# hvSdbSchematic.net
KiCad netlist of a schematic drawn in Altium Designer
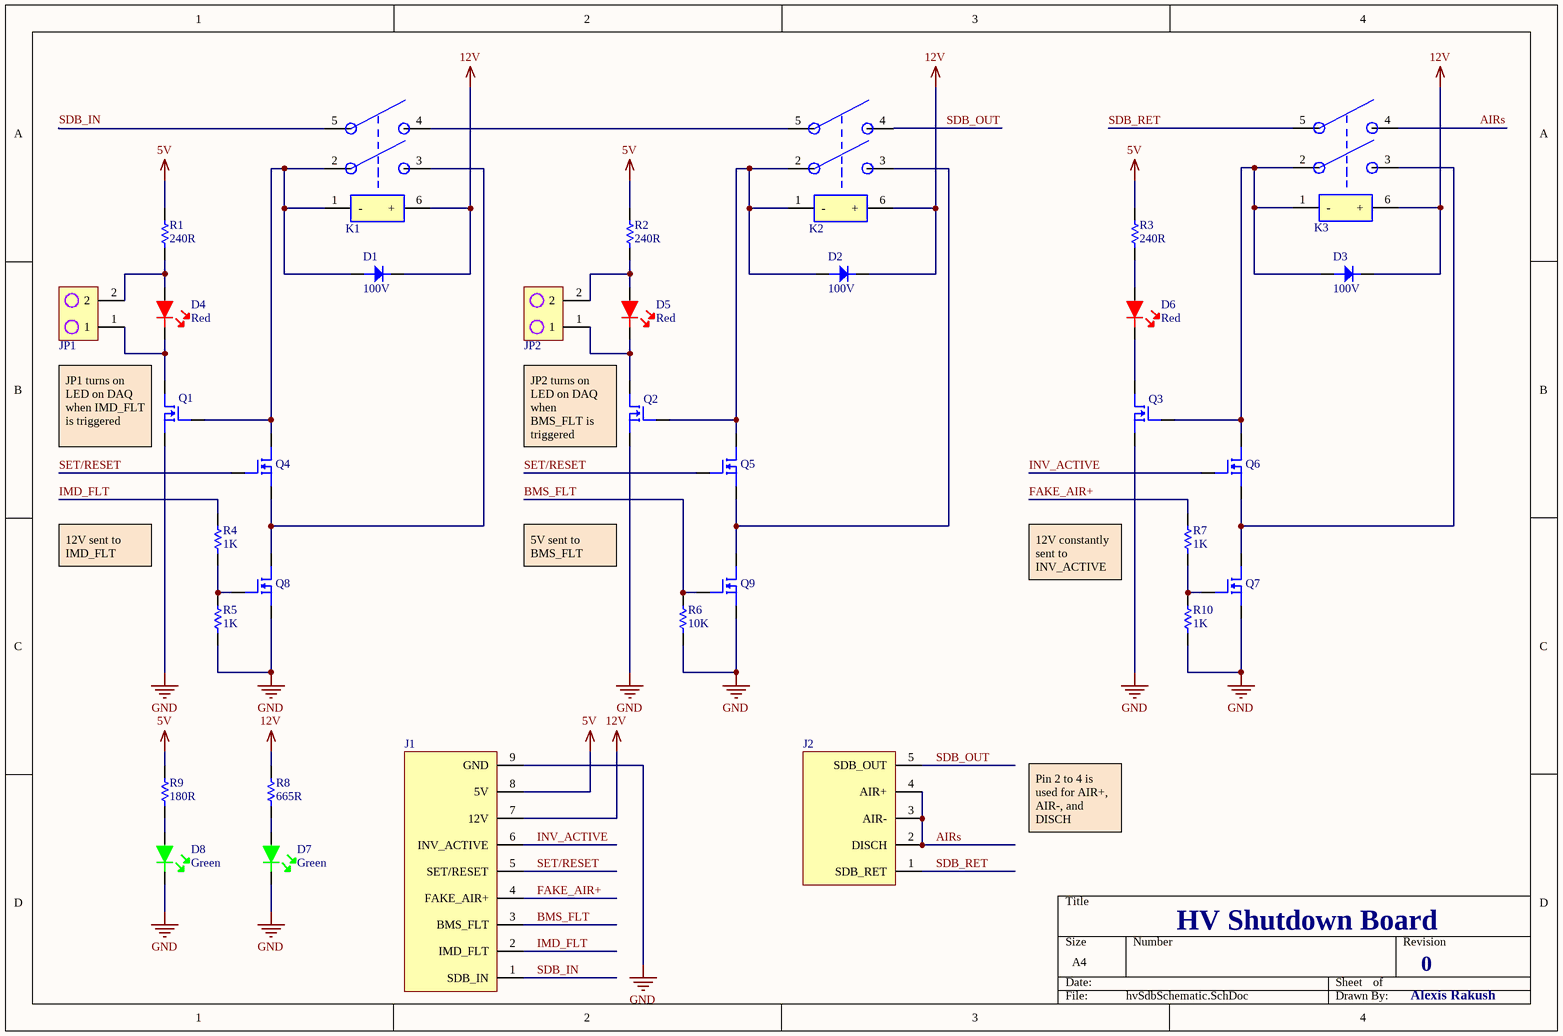
[diagram p0: hvSdbSchematic.SchDoc]

(export (version "E")
  (design (tool "Eeschema 10.0.6"))
  (components
    (comp (ref "D1")
      (value "100V")
      (footprint "DO-214AA")
      (description "DIODE GEN PURP 100V 3A DO214AA")
      (fields (field (name "MANUFACTURER") "MCC") (field (name "MANUFACTURER PART NUMBER") "S3BB-TP"))
      (libsource (lib "hvSdbSchLib") (part "Diode-100V-3A"))
    )
    (comp (ref "D2")
      (value "100V")
      (footprint "DO-214AA")
      (description "DIODE GEN PURP 100V 3A DO214AA")
      (fields (field (name "MANUFACTURER") "MCC") (field (name "MANUFACTURER PART NUMBER") "S3BB-TP"))
      (libsource (lib "hvSdbSchLib") (part "Diode-100V-3A"))
    )
    (comp (ref "D3")
      (value "100V")
      (footprint "DO-214AA")
      (description "DIODE GEN PURP 100V 3A DO214AA")
      (fields (field (name "MANUFACTURER") "MCC") (field (name "MANUFACTURER PART NUMBER") "S3BB-TP"))
      (libsource (lib "hvSdbSchLib") (part "Diode-100V-3A"))
    )
    (comp (ref "D4")
      (value "Red")
      (footprint "LED-0603")
      (description "LED RED CLEAR 0603 SMD")
      (fields
        (field (name "MANUFACTURER") "Wurth Electronics")
        (field (name "MANUFACTURER PART NUMBER") "150060RS75000")
      )
      (libsource (lib "hvSdbSchLib") (part "LED-Red"))
    )
    (comp (ref "D5")
      (value "Red")
      (footprint "LED-0603")
      (description "LED RED CLEAR 0603 SMD")
      (fields
        (field (name "MANUFACTURER") "Wurth Electronics")
        (field (name "MANUFACTURER PART NUMBER") "150060RS75000")
      )
      (libsource (lib "hvSdbSchLib") (part "LED-Red"))
    )
    (comp (ref "D6")
      (value "Red")
      (footprint "LED-0603")
      (description "LED RED CLEAR 0603 SMD")
      (fields
        (field (name "MANUFACTURER") "Wurth Electronics")
        (field (name "MANUFACTURER PART NUMBER") "150060RS75000")
      )
      (libsource (lib "hvSdbSchLib") (part "LED-Red"))
    )
    (comp (ref "D7")
      (value "Green")
      (footprint "LED-0603")
      (description "LED GREEN CLEAR 0603 SMD")
      (fields
        (field (name "MANUFACTURER") "Wurth Electronics")
        (field (name "MANUFACTURER PART NUMBER") "150060VS75000")
      )
      (libsource (lib "hvSdbSchLib") (part "LED-Green"))
    )
    (comp (ref "D8")
      (value "Green")
      (footprint "LED-0603")
      (description "LED GREEN CLEAR 0603 SMD")
      (fields
        (field (name "MANUFACTURER") "Wurth Electronics")
        (field (name "MANUFACTURER PART NUMBER") "150060VS75000")
      )
      (libsource (lib "hvSdbSchLib") (part "LED-Green"))
    )
    (comp (ref "J1")
      (value "23-0705530113-ND")
      (footprint "9PIN")
      (description "CONN HEADER R/A 9POS 2.54MM")
      (fields (field (name "MANUFACTURER") "Molex") (field (name "MANUFACTURER PART NUMBER") "70553-0112"))
      (libsource (lib "hvSdbSchLib") (part "9PIN"))
    )
    (comp (ref "J2")
      (value "WM4903-ND")
      (footprint "5PIN")
      (description "CONN HEADER R/A 5POS 2.54MM")
      (fields (field (name "MANUFACTURER") "Molex") (field (name "MANUFACTURER PART NUMBER") "0705530004"))
      (libsource (lib "hvSdbSchLib") (part "5PIN"))
    )
    (comp (ref "JP1")
      (value "732-5315-ND")
      (footprint "2PIN-JP")
      (description "CONN HEADER VERT 2POS 2.54MM")
      (libsource (lib "hvSdbSchLib") (part "2PIN-TEST"))
    )
    (comp (ref "JP2")
      (value "732-5315-ND")
      (footprint "2PIN-JP")
      (description "CONN HEADER VERT 2POS 2.54MM")
      (libsource (lib "hvSdbSchLib") (part "2PIN-TEST"))
    )
    (comp (ref "K1")
      (value "5-1419124-6")
      (footprint "RELAY DPST SDC")
      (description "General Purpose Relay, Osa Series, Power, Non Latching, Dpst-No, 12 Vdc, 3 A Rohs Compliant: Yes")
      (fields (field (name "MANUFACTURER") "TE Connectivity"))
      (libsource (lib "hvSdbSchLib") (part "5-1419124-6"))
    )
    (comp (ref "K2")
      (value "5-1419124-6")
      (footprint "RELAY DPST SDC")
      (description "General Purpose Relay, Osa Series, Power, Non Latching, Dpst-No, 12 Vdc, 3 A Rohs Compliant: Yes")
      (fields (field (name "MANUFACTURER") "TE Connectivity"))
      (libsource (lib "hvSdbSchLib") (part "5-1419124-6"))
    )
    (comp (ref "K3")
      (value "5-1419124-6")
      (footprint "RELAY DPST SDC")
      (description "General Purpose Relay, Osa Series, Power, Non Latching, Dpst-No, 12 Vdc, 3 A Rohs Compliant: Yes")
      (fields (field (name "MANUFACTURER") "TE Connectivity"))
      (libsource (lib "hvSdbSchLib") (part "5-1419124-6"))
    )
    (comp (ref "Q1")
      (value "DMN6140L-13DICT-ND")
      (footprint "SOT-23-3")
      (description "MOSFET N-CH 60V 1.6A SOT23")
      (fields (field (name "MANUFACTURER") "Diodes") (field (name "MANUFACTURER PART NUMBER") "DMN6140L-13"))
      (libsource (lib "hvSdbSchLib") (part "N-FET-60V-1.6A"))
    )
    (comp (ref "Q2")
      (value "DMN6140L-13DICT-ND")
      (footprint "SOT-23-3")
      (description "MOSFET N-CH 60V 1.6A SOT23")
      (fields (field (name "MANUFACTURER") "Diodes") (field (name "MANUFACTURER PART NUMBER") "DMN6140L-13"))
      (libsource (lib "hvSdbSchLib") (part "N-FET-60V-1.6A"))
    )
    (comp (ref "Q3")
      (value "DMN6140L-13DICT-ND")
      (footprint "SOT-23-3")
      (description "MOSFET N-CH 60V 1.6A SOT23")
      (fields (field (name "MANUFACTURER") "Diodes") (field (name "MANUFACTURER PART NUMBER") "DMN6140L-13"))
      (libsource (lib "hvSdbSchLib") (part "N-FET-60V-1.6A"))
    )
    (comp (ref "Q4")
      (value "DMN6140L-13DICT-ND")
      (footprint "SOT-23-3")
      (description "MOSFET N-CH 60V 1.6A SOT23")
      (fields (field (name "MANUFACTURER") "Diodes") (field (name "MANUFACTURER PART NUMBER") "DMN6140L-13"))
      (libsource (lib "hvSdbSchLib") (part "N-FET-60V-1.6A"))
    )
    (comp (ref "Q5")
      (value "DMN6140L-13DICT-ND")
      (footprint "SOT-23-3")
      (description "MOSFET N-CH 60V 1.6A SOT23")
      (fields (field (name "MANUFACTURER") "Diodes") (field (name "MANUFACTURER PART NUMBER") "DMN6140L-13"))
      (libsource (lib "hvSdbSchLib") (part "N-FET-60V-1.6A"))
    )
    (comp (ref "Q6")
      (value "DMN6140L-13DICT-ND")
      (footprint "SOT-23-3")
      (description "MOSFET N-CH 60V 1.6A SOT23")
      (fields (field (name "MANUFACTURER") "Diodes") (field (name "MANUFACTURER PART NUMBER") "DMN6140L-13"))
      (libsource (lib "hvSdbSchLib") (part "N-FET-60V-1.6A"))
    )
    (comp (ref "Q7")
      (value "DMN6140L-13DICT-ND")
      (footprint "SOT-23-3")
      (description "MOSFET N-CH 60V 1.6A SOT23")
      (fields (field (name "MANUFACTURER") "Diodes") (field (name "MANUFACTURER PART NUMBER") "DMN6140L-13"))
      (libsource (lib "hvSdbSchLib") (part "N-FET-60V-1.6A"))
    )
    (comp (ref "Q8")
      (value "DMN6140L-13DICT-ND")
      (footprint "SOT-23-3")
      (description "MOSFET N-CH 60V 1.6A SOT23")
      (fields (field (name "MANUFACTURER") "Diodes") (field (name "MANUFACTURER PART NUMBER") "DMN6140L-13"))
      (libsource (lib "hvSdbSchLib") (part "N-FET-60V-1.6A"))
    )
    (comp (ref "Q9")
      (value "DMN6140L-13DICT-ND")
      (footprint "SOT-23-3")
      (description "MOSFET N-CH 60V 1.6A SOT23")
      (fields (field (name "MANUFACTURER") "Diodes") (field (name "MANUFACTURER PART NUMBER") "DMN6140L-13"))
      (libsource (lib "hvSdbSchLib") (part "N-FET-60V-1.6A"))
    )
    (comp (ref "R1")
      (value "240R")
      (footprint "RES-0603")
      (description "RES 240 OHM 1% 1/10W 0603")
      (fields
        (field (name "MANUFACTURER") "Stackpole Electronics")
        (field (name "MANUFACTURER PART NUMBER") "RMCF0603FT240R")
      )
      (libsource (lib "hvSdbSchLib") (part "0603-240R"))
    )
    (comp (ref "R2")
      (value "240R")
      (footprint "RES-0603")
      (description "RES 240 OHM 1% 1/10W 0603")
      (fields
        (field (name "MANUFACTURER") "Stackpole Electronics")
        (field (name "MANUFACTURER PART NUMBER") "RMCF0603FT240R")
      )
      (libsource (lib "hvSdbSchLib") (part "0603-240R"))
    )
    (comp (ref "R3")
      (value "240R")
      (footprint "RES-0603")
      (description "RES 240 OHM 1% 1/10W 0603")
      (fields
        (field (name "MANUFACTURER") "Stackpole Electronics")
        (field (name "MANUFACTURER PART NUMBER") "RMCF0603FT240R")
      )
      (libsource (lib "hvSdbSchLib") (part "0603-240R"))
    )
    (comp (ref "R4")
      (value "1K")
      (footprint "RES-0603")
      (description "RES SMD 1K OHM 1% 1/10W 0603")
      (fields
        (field (name "MANUFACTURER") "Vishay Dale")
        (field (name "MANUFACTURER PART NUMBER") "CRCW06031K00FKEA")
      )
      (libsource (lib "hvSdbSchLib") (part "0603-1KR"))
    )
    (comp (ref "R5")
      (value "1K")
      (footprint "RES-0603")
      (description "RES SMD 1K OHM 1% 1/10W 0603")
      (fields
        (field (name "MANUFACTURER") "Vishay Dale")
        (field (name "MANUFACTURER PART NUMBER") "CRCW06031K00FKEA")
      )
      (libsource (lib "hvSdbSchLib") (part "0603-1KR"))
    )
    (comp (ref "R6")
      (value "10K")
      (footprint "RES-0603")
      (description "RES SMD 10K OHM 5% 1/10W 0603")
      (fields
        (field (name "MANUFACTURER") "Yageo")
        (field (name "MANUFACTURER PART NUMBER") "RC0603JR-0710KL")
      )
      (libsource (lib "hvSdbSchLib") (part "0603-10KR"))
    )
    (comp (ref "R7")
      (value "1K")
      (footprint "RES-0603")
      (description "RES SMD 1K OHM 1% 1/10W 0603")
      (fields
        (field (name "MANUFACTURER") "Vishay Dale")
        (field (name "MANUFACTURER PART NUMBER") "CRCW06031K00FKEA")
      )
      (libsource (lib "hvSdbSchLib") (part "0603-1KR"))
    )
    (comp (ref "R8")
      (value "665R")
      (footprint "RES-0603")
      (description "RES SMD 665 OHM 1% 1/10W 0603")
      (fields
        (field (name "MANUFACTURER") "Yageo")
        (field (name "MANUFACTURER PART NUMBER") "RC0603FR-07665RL")
      )
      (libsource (lib "hvSdbSchLib") (part "0603-665R"))
    )
    (comp (ref "R9")
      (value "180R")
      (footprint "RES-0603")
      (description "RES SMD 180 OHM 1% 1/10W 0603")
      (fields
        (field (name "MANUFACTURER") "TE Connectivity")
        (field (name "MANUFACTURER PART NUMBER") "CRGCQ0603F180R")
      )
      (libsource (lib "hvSdbSchLib") (part "0603-180R"))
    )
    (comp (ref "R10")
      (value "1K")
      (footprint "RES-0603")
      (description "RES SMD 1K OHM 1% 1/10W 0603")
      (fields
        (field (name "MANUFACTURER") "Vishay Dale")
        (field (name "MANUFACTURER PART NUMBER") "CRCW06031K00FKEA")
      )
      (libsource (lib "hvSdbSchLib") (part "0603-1KR"))
    )
  )
  (nets
    (net (code "1") (name "/AIRs") (class "Default")
      (node (ref "J2") (pin "2") (pinfunction "DISCH_2") (pintype "passive"))
      (node (ref "J2") (pin "3") (pinfunction "AIR-_3") (pintype "passive"))
      (node (ref "J2") (pin "4") (pinfunction "AIR+_4") (pintype "passive"))
      (node (ref "K3") (pin "4") (pintype "passive"))
    )
    (net (code "2") (name "/BMS_FLT") (class "Default")
      (node (ref "J1") (pin "3") (pinfunction "BMS_FLT_3") (pintype "passive"))
      (node (ref "Q9") (pin "1") (pinfunction "1_1") (pintype "passive"))
      (node (ref "R6") (pin "2") (pinfunction "2_2") (pintype "passive"))
    )
    (net (code "3") (name "/FAKE_AIR+") (class "Default")
      (node (ref "J1") (pin "4") (pinfunction "FAKE_AIR+_4") (pintype "passive"))
      (node (ref "R7") (pin "2") (pinfunction "2_2") (pintype "passive"))
    )
    (net (code "4") (name "/IMD_FLT") (class "Default")
      (node (ref "J1") (pin "2") (pinfunction "IMD_FLT_2") (pintype "passive"))
      (node (ref "R4") (pin "2") (pinfunction "2_2") (pintype "passive"))
    )
    (net (code "5") (name "/INV_ACTIVE") (class "Default")
      (node (ref "J1") (pin "6") (pinfunction "INV_ACTIVE_6") (pintype "passive"))
      (node (ref "Q6") (pin "1") (pinfunction "1_1") (pintype "passive"))
    )
    (net (code "6") (name "/SDB_IN") (class "Default")
      (node (ref "J1") (pin "1") (pinfunction "SDB_IN_1") (pintype "passive"))
      (node (ref "K1") (pin "5") (pintype "passive"))
    )
    (net (code "7") (name "/SDB_OUT") (class "Default")
      (node (ref "J2") (pin "5") (pinfunction "SDB_OUT_5") (pintype "passive"))
      (node (ref "K2") (pin "4") (pintype "passive"))
    )
    (net (code "8") (name "/SDB_RET") (class "Default")
      (node (ref "J2") (pin "1") (pinfunction "SDB_RET_1") (pintype "passive"))
      (node (ref "K3") (pin "5") (pintype "passive"))
    )
    (net (code "9") (name "/SET{slash}RESET") (class "Default")
      (node (ref "J1") (pin "5") (pinfunction "SET/RESET_5") (pintype "passive"))
      (node (ref "Q4") (pin "1") (pinfunction "1_1") (pintype "passive"))
      (node (ref "Q5") (pin "1") (pinfunction "1_1") (pintype "passive"))
    )
    (net (code "10") (name "5V") (class "Default")
      (node (ref "J1") (pin "8") (pinfunction "5V_8") (pintype "passive"))
      (node (ref "R1") (pin "2") (pinfunction "2_2") (pintype "passive"))
      (node (ref "R2") (pin "2") (pinfunction "2_2") (pintype "passive"))
      (node (ref "R3") (pin "2") (pinfunction "2_2") (pintype "passive"))
      (node (ref "R9") (pin "2") (pinfunction "2_2") (pintype "passive"))
    )
    (net (code "11") (name "12V") (class "Default")
      (node (ref "D1") (pin "1") (pinfunction "1_1") (pintype "passive"))
      (node (ref "D2") (pin "1") (pinfunction "1_1") (pintype "passive"))
      (node (ref "D3") (pin "1") (pinfunction "1_1") (pintype "passive"))
      (node (ref "J1") (pin "7") (pinfunction "12V_7") (pintype "passive"))
      (node (ref "K1") (pin "6") (pinfunction "+_6") (pintype "passive"))
      (node (ref "K2") (pin "6") (pinfunction "+_6") (pintype "passive"))
      (node (ref "K3") (pin "6") (pinfunction "+_6") (pintype "passive"))
      (node (ref "R8") (pin "2") (pinfunction "2_2") (pintype "passive"))
    )
    (net (code "12") (name "GND") (class "Default")
      (node (ref "D7") (pin "2") (pinfunction "2_2") (pintype "passive"))
      (node (ref "D8") (pin "2") (pinfunction "2_2") (pintype "passive"))
      (node (ref "J1") (pin "9") (pinfunction "GND_9") (pintype "passive"))
      (node (ref "Q1") (pin "3") (pinfunction "3_3") (pintype "passive"))
      (node (ref "Q2") (pin "3") (pinfunction "3_3") (pintype "passive"))
      (node (ref "Q3") (pin "3") (pinfunction "3_3") (pintype "passive"))
      (node (ref "Q7") (pin "3") (pinfunction "3_3") (pintype "passive"))
      (node (ref "Q8") (pin "3") (pinfunction "3_3") (pintype "passive"))
      (node (ref "Q9") (pin "3") (pinfunction "3_3") (pintype "passive"))
      (node (ref "R10") (pin "1") (pinfunction "1_1") (pintype "passive"))
      (node (ref "R5") (pin "1") (pinfunction "1_1") (pintype "passive"))
      (node (ref "R6") (pin "1") (pinfunction "1_1") (pintype "passive"))
    )
    (net (code "13") (name "Net-(D4-Pad1)") (class "Default")
      (node (ref "D4") (pin "1") (pinfunction "1_1") (pintype "passive"))
      (node (ref "JP1") (pin "2") (pinfunction "2_2") (pintype "passive"))
      (node (ref "R1") (pin "1") (pinfunction "1_1") (pintype "passive"))
    )
    (net (code "14") (name "Net-(D4-Pad2)") (class "Default")
      (node (ref "D4") (pin "2") (pinfunction "2_2") (pintype "passive"))
      (node (ref "JP1") (pin "1") (pinfunction "1_1") (pintype "passive"))
      (node (ref "Q1") (pin "2") (pinfunction "2_2") (pintype "passive"))
    )
    (net (code "15") (name "Net-(D5-Pad1)") (class "Default")
      (node (ref "D5") (pin "1") (pinfunction "1_1") (pintype "passive"))
      (node (ref "JP2") (pin "2") (pinfunction "2_2") (pintype "passive"))
      (node (ref "R2") (pin "1") (pinfunction "1_1") (pintype "passive"))
    )
    (net (code "16") (name "Net-(D5-Pad2)") (class "Default")
      (node (ref "D5") (pin "2") (pinfunction "2_2") (pintype "passive"))
      (node (ref "JP2") (pin "1") (pinfunction "1_1") (pintype "passive"))
      (node (ref "Q2") (pin "2") (pinfunction "2_2") (pintype "passive"))
    )
    (net (code "17") (name "Net-(D6-Pad1)") (class "Default")
      (node (ref "D6") (pin "1") (pinfunction "1_1") (pintype "passive"))
      (node (ref "R3") (pin "1") (pinfunction "1_1") (pintype "passive"))
    )
    (net (code "18") (name "Net-(D6-Pad2)") (class "Default")
      (node (ref "D6") (pin "2") (pinfunction "2_2") (pintype "passive"))
      (node (ref "Q3") (pin "2") (pinfunction "2_2") (pintype "passive"))
    )
    (net (code "19") (name "Net-(D7-Pad1)") (class "Default")
      (node (ref "D7") (pin "1") (pinfunction "1_1") (pintype "passive"))
      (node (ref "R8") (pin "1") (pinfunction "1_1") (pintype "passive"))
    )
    (net (code "20") (name "Net-(D8-Pad1)") (class "Default")
      (node (ref "D8") (pin "1") (pinfunction "1_1") (pintype "passive"))
      (node (ref "R9") (pin "1") (pinfunction "1_1") (pintype "passive"))
    )
    (net (code "21") (name "Net-(K1--)") (class "Default")
      (node (ref "D1") (pin "2") (pinfunction "2_2") (pintype "passive"))
      (node (ref "K1") (pin "1") (pinfunction "-_1") (pintype "passive"))
      (node (ref "K1") (pin "2") (pintype "passive"))
      (node (ref "Q1") (pin "1") (pinfunction "1_1") (pintype "passive"))
      (node (ref "Q4") (pin "2") (pinfunction "2_2") (pintype "passive"))
    )
    (net (code "22") (name "Net-(K1-Pad3)") (class "Default")
      (node (ref "K1") (pin "3") (pintype "passive"))
      (node (ref "Q4") (pin "3") (pinfunction "3_3") (pintype "passive"))
      (node (ref "Q8") (pin "2") (pinfunction "2_2") (pintype "passive"))
    )
    (net (code "23") (name "Net-(K1-Pad4)") (class "Default")
      (node (ref "K1") (pin "4") (pintype "passive"))
      (node (ref "K2") (pin "5") (pintype "passive"))
    )
    (net (code "24") (name "Net-(K2--)") (class "Default")
      (node (ref "D2") (pin "2") (pinfunction "2_2") (pintype "passive"))
      (node (ref "K2") (pin "1") (pinfunction "-_1") (pintype "passive"))
      (node (ref "K2") (pin "2") (pintype "passive"))
      (node (ref "Q2") (pin "1") (pinfunction "1_1") (pintype "passive"))
      (node (ref "Q5") (pin "2") (pinfunction "2_2") (pintype "passive"))
    )
    (net (code "25") (name "Net-(K2-Pad3)") (class "Default")
      (node (ref "K2") (pin "3") (pintype "passive"))
      (node (ref "Q5") (pin "3") (pinfunction "3_3") (pintype "passive"))
      (node (ref "Q9") (pin "2") (pinfunction "2_2") (pintype "passive"))
    )
    (net (code "26") (name "Net-(K3--)") (class "Default")
      (node (ref "D3") (pin "2") (pinfunction "2_2") (pintype "passive"))
      (node (ref "K3") (pin "1") (pinfunction "-_1") (pintype "passive"))
      (node (ref "K3") (pin "2") (pintype "passive"))
      (node (ref "Q3") (pin "1") (pinfunction "1_1") (pintype "passive"))
      (node (ref "Q6") (pin "2") (pinfunction "2_2") (pintype "passive"))
    )
    (net (code "27") (name "Net-(K3-Pad3)") (class "Default")
      (node (ref "K3") (pin "3") (pintype "passive"))
      (node (ref "Q6") (pin "3") (pinfunction "3_3") (pintype "passive"))
      (node (ref "Q7") (pin "2") (pinfunction "2_2") (pintype "passive"))
    )
    (net (code "28") (name "Net-(Q7-Pad1)") (class "Default")
      (node (ref "Q7") (pin "1") (pinfunction "1_1") (pintype "passive"))
      (node (ref "R10") (pin "2") (pinfunction "2_2") (pintype "passive"))
      (node (ref "R7") (pin "1") (pinfunction "1_1") (pintype "passive"))
    )
    (net (code "29") (name "Net-(Q8-Pad1)") (class "Default")
      (node (ref "Q8") (pin "1") (pinfunction "1_1") (pintype "passive"))
      (node (ref "R4") (pin "1") (pinfunction "1_1") (pintype "passive"))
      (node (ref "R5") (pin "2") (pinfunction "2_2") (pintype "passive"))
    )
  )
)
